# source_eagle.net
KiCad netlist of a schematic drawn in EAGLE
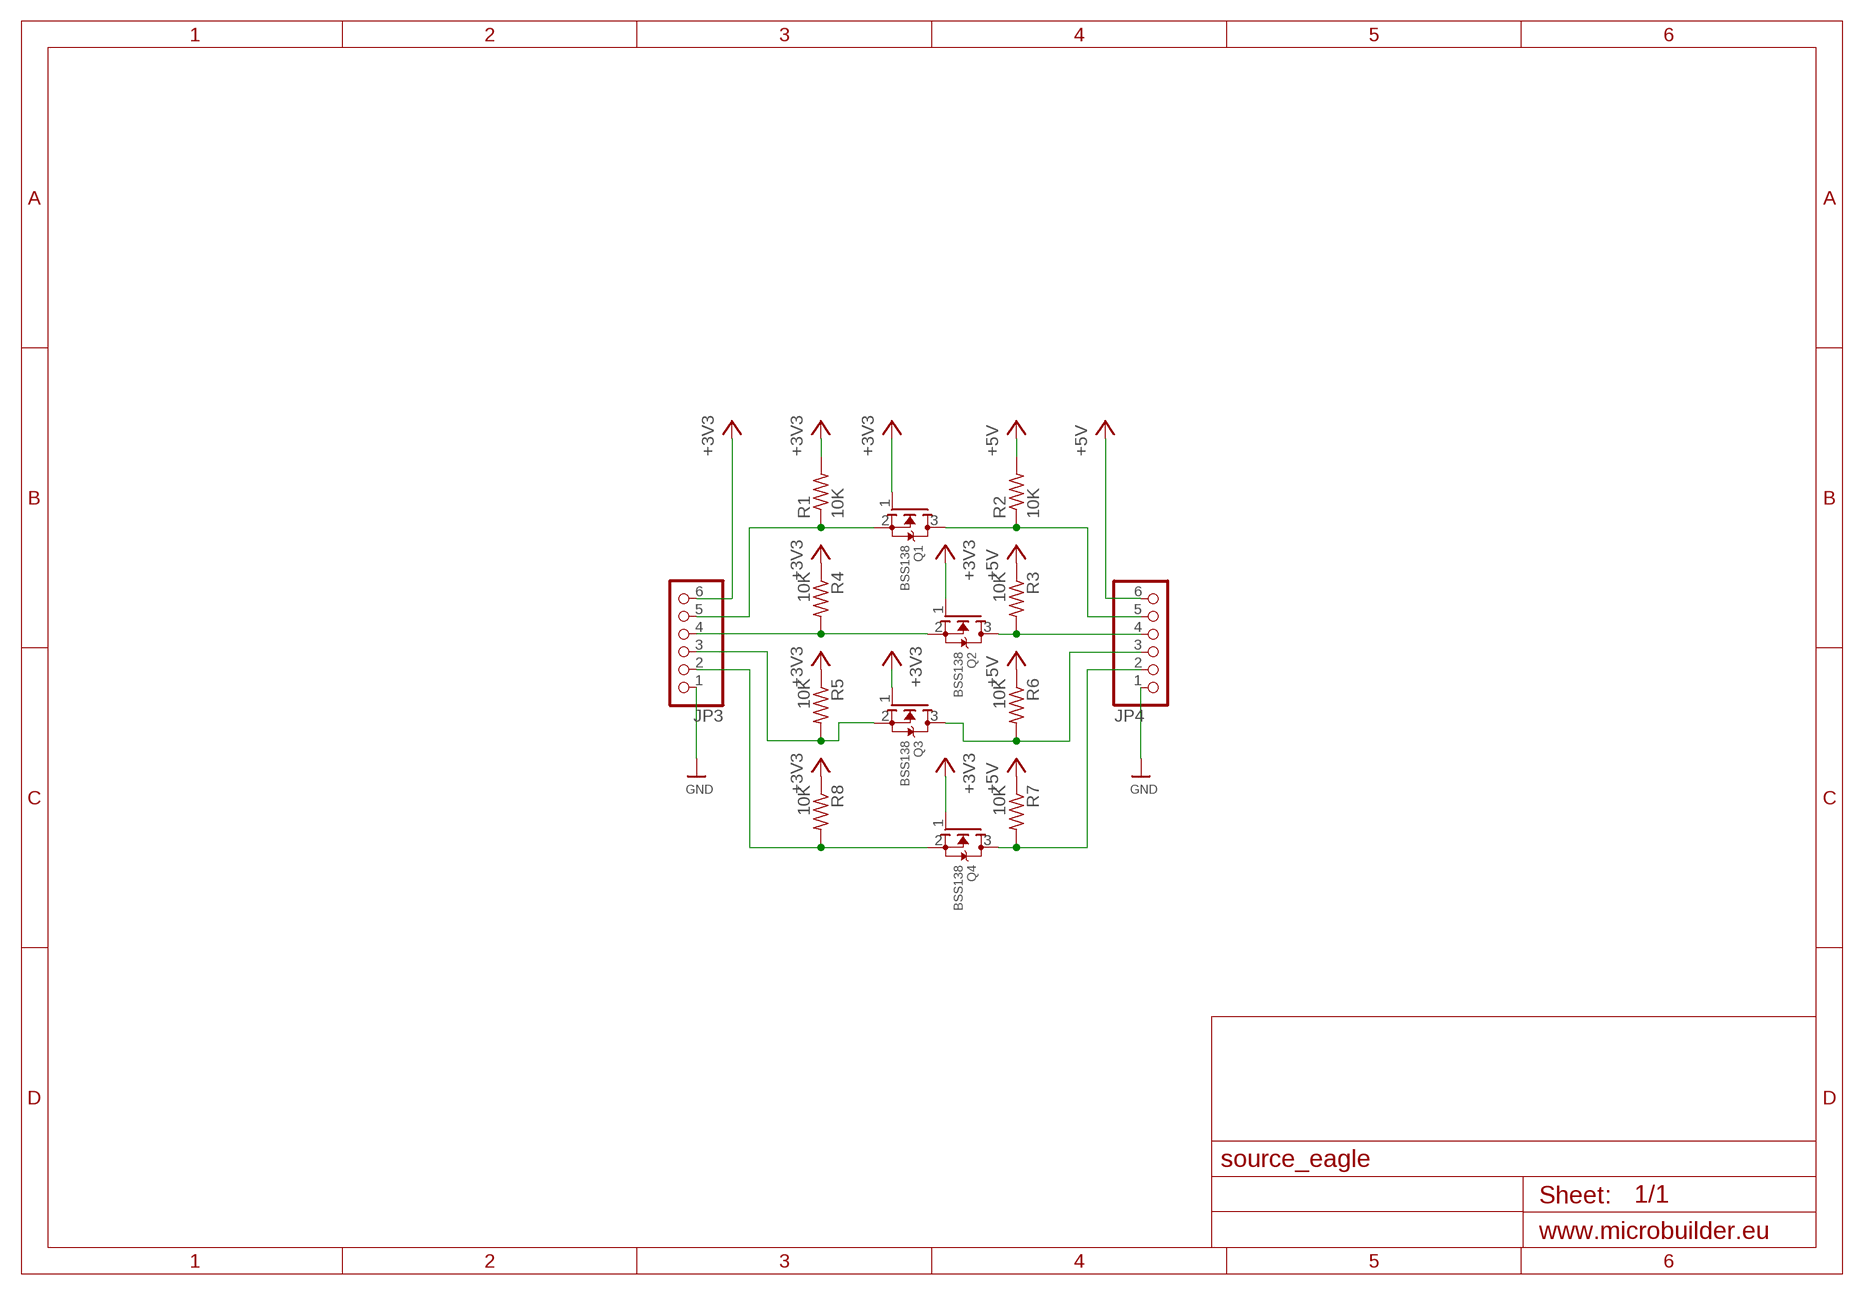
[diagram p0: schematic, sheet 1]

(export (version "E")
  (design (tool "Eeschema 10.0.6"))
  (components
    (comp (ref "JP3")
      (value "PINHD-1X6CB")
      (footprint "eagle-import:1X06-CLEANBIG")
      (libsource (lib "eagle-import") (part "PINHD-1X6CB"))
    )
    (comp (ref "JP4")
      (value "PINHD-1X6CB")
      (footprint "eagle-import:1X06-CLEANBIG")
      (libsource (lib "eagle-import") (part "PINHD-1X6CB"))
    )
    (comp (ref "Q1")
      (value "BSS138")
      (footprint "eagle-import:SOT23")
      (libsource (lib "eagle-import") (part "MOSFET-NREFLOW"))
    )
    (comp (ref "Q2")
      (value "BSS138")
      (footprint "eagle-import:SOT23")
      (libsource (lib "eagle-import") (part "MOSFET-NREFLOW"))
    )
    (comp (ref "Q3")
      (value "BSS138")
      (footprint "eagle-import:SOT23")
      (libsource (lib "eagle-import") (part "MOSFET-NREFLOW"))
    )
    (comp (ref "Q4")
      (value "BSS138")
      (footprint "eagle-import:SOT23")
      (libsource (lib "eagle-import") (part "MOSFET-NREFLOW"))
    )
    (comp (ref "R1")
      (value "10K")
      (footprint "eagle-import:R0805")
      (libsource (lib "eagle-import") (part "R-US_R0805"))
    )
    (comp (ref "R2")
      (value "10K")
      (footprint "eagle-import:R0805")
      (libsource (lib "eagle-import") (part "R-US_R0805"))
    )
    (comp (ref "R3")
      (value "10K")
      (footprint "eagle-import:R0805")
      (libsource (lib "eagle-import") (part "R-US_R0805"))
    )
    (comp (ref "R4")
      (value "10K")
      (footprint "eagle-import:R0805")
      (libsource (lib "eagle-import") (part "R-US_R0805"))
    )
    (comp (ref "R5")
      (value "10K")
      (footprint "eagle-import:R0805")
      (libsource (lib "eagle-import") (part "R-US_R0805"))
    )
    (comp (ref "R6")
      (value "10K")
      (footprint "eagle-import:R0805")
      (libsource (lib "eagle-import") (part "R-US_R0805"))
    )
    (comp (ref "R7")
      (value "10K")
      (footprint "eagle-import:R0805")
      (libsource (lib "eagle-import") (part "R-US_R0805"))
    )
    (comp (ref "R8")
      (value "10K")
      (footprint "eagle-import:R0805")
      (libsource (lib "eagle-import") (part "R-US_R0805"))
    )
  )
  (nets
    (net (code "1") (name "+3V3") (class "Default")
      (node (ref "JP3") (pin "6") (pinfunction "6_6") (pintype "passive"))
      (node (ref "Q1") (pin "1") (pinfunction "G_1") (pintype "bidirectional"))
      (node (ref "Q2") (pin "1") (pinfunction "G_1") (pintype "bidirectional"))
      (node (ref "Q3") (pin "1") (pinfunction "G_1") (pintype "bidirectional"))
      (node (ref "Q4") (pin "1") (pinfunction "G_1") (pintype "bidirectional"))
      (node (ref "R1") (pin "2") (pinfunction "2_2") (pintype "passive"))
      (node (ref "R4") (pin "1") (pinfunction "1_1") (pintype "passive"))
      (node (ref "R5") (pin "1") (pinfunction "1_1") (pintype "passive"))
      (node (ref "R8") (pin "1") (pinfunction "1_1") (pintype "passive"))
    )
    (net (code "2") (name "+5V") (class "Default")
      (node (ref "JP4") (pin "6") (pinfunction "6_6") (pintype "passive"))
      (node (ref "R2") (pin "2") (pinfunction "2_2") (pintype "passive"))
      (node (ref "R3") (pin "1") (pinfunction "1_1") (pintype "passive"))
      (node (ref "R6") (pin "1") (pinfunction "1_1") (pintype "passive"))
      (node (ref "R7") (pin "1") (pinfunction "1_1") (pintype "passive"))
    )
    (net (code "3") (name "GND") (class "Default")
      (node (ref "JP3") (pin "1") (pinfunction "1_1") (pintype "passive"))
      (node (ref "JP4") (pin "1") (pinfunction "1_1") (pintype "passive"))
    )
    (net (code "4") (name "Net-(Q1-D)") (class "Default")
      (node (ref "JP4") (pin "5") (pinfunction "5_5") (pintype "passive"))
      (node (ref "Q1") (pin "3") (pinfunction "D_3") (pintype "bidirectional"))
      (node (ref "R2") (pin "1") (pinfunction "1_1") (pintype "passive"))
    )
    (net (code "5") (name "Net-(Q1-S)") (class "Default")
      (node (ref "JP3") (pin "5") (pinfunction "5_5") (pintype "passive"))
      (node (ref "Q1") (pin "2") (pinfunction "S_2") (pintype "bidirectional"))
      (node (ref "R1") (pin "1") (pinfunction "1_1") (pintype "passive"))
    )
    (net (code "6") (name "Net-(Q2-D)") (class "Default")
      (node (ref "JP4") (pin "4") (pinfunction "4_4") (pintype "passive"))
      (node (ref "Q2") (pin "3") (pinfunction "D_3") (pintype "bidirectional"))
      (node (ref "R3") (pin "2") (pinfunction "2_2") (pintype "passive"))
    )
    (net (code "7") (name "Net-(Q2-S)") (class "Default")
      (node (ref "JP3") (pin "4") (pinfunction "4_4") (pintype "passive"))
      (node (ref "Q2") (pin "2") (pinfunction "S_2") (pintype "bidirectional"))
      (node (ref "R4") (pin "2") (pinfunction "2_2") (pintype "passive"))
    )
    (net (code "8") (name "Net-(Q3-D)") (class "Default")
      (node (ref "JP4") (pin "3") (pinfunction "3_3") (pintype "passive"))
      (node (ref "Q3") (pin "3") (pinfunction "D_3") (pintype "bidirectional"))
      (node (ref "R6") (pin "2") (pinfunction "2_2") (pintype "passive"))
    )
    (net (code "9") (name "Net-(Q3-S)") (class "Default")
      (node (ref "JP3") (pin "3") (pinfunction "3_3") (pintype "passive"))
      (node (ref "Q3") (pin "2") (pinfunction "S_2") (pintype "bidirectional"))
      (node (ref "R5") (pin "2") (pinfunction "2_2") (pintype "passive"))
    )
    (net (code "10") (name "Net-(Q4-D)") (class "Default")
      (node (ref "JP4") (pin "2") (pinfunction "2_2") (pintype "passive"))
      (node (ref "Q4") (pin "3") (pinfunction "D_3") (pintype "bidirectional"))
      (node (ref "R7") (pin "2") (pinfunction "2_2") (pintype "passive"))
    )
    (net (code "11") (name "Net-(Q4-S)") (class "Default")
      (node (ref "JP3") (pin "2") (pinfunction "2_2") (pintype "passive"))
      (node (ref "Q4") (pin "2") (pinfunction "S_2") (pintype "bidirectional"))
      (node (ref "R8") (pin "2") (pinfunction "2_2") (pintype "passive"))
    )
  )
)
